# christmas_card.net
KiCad netlist of a schematic drawn in EAGLE
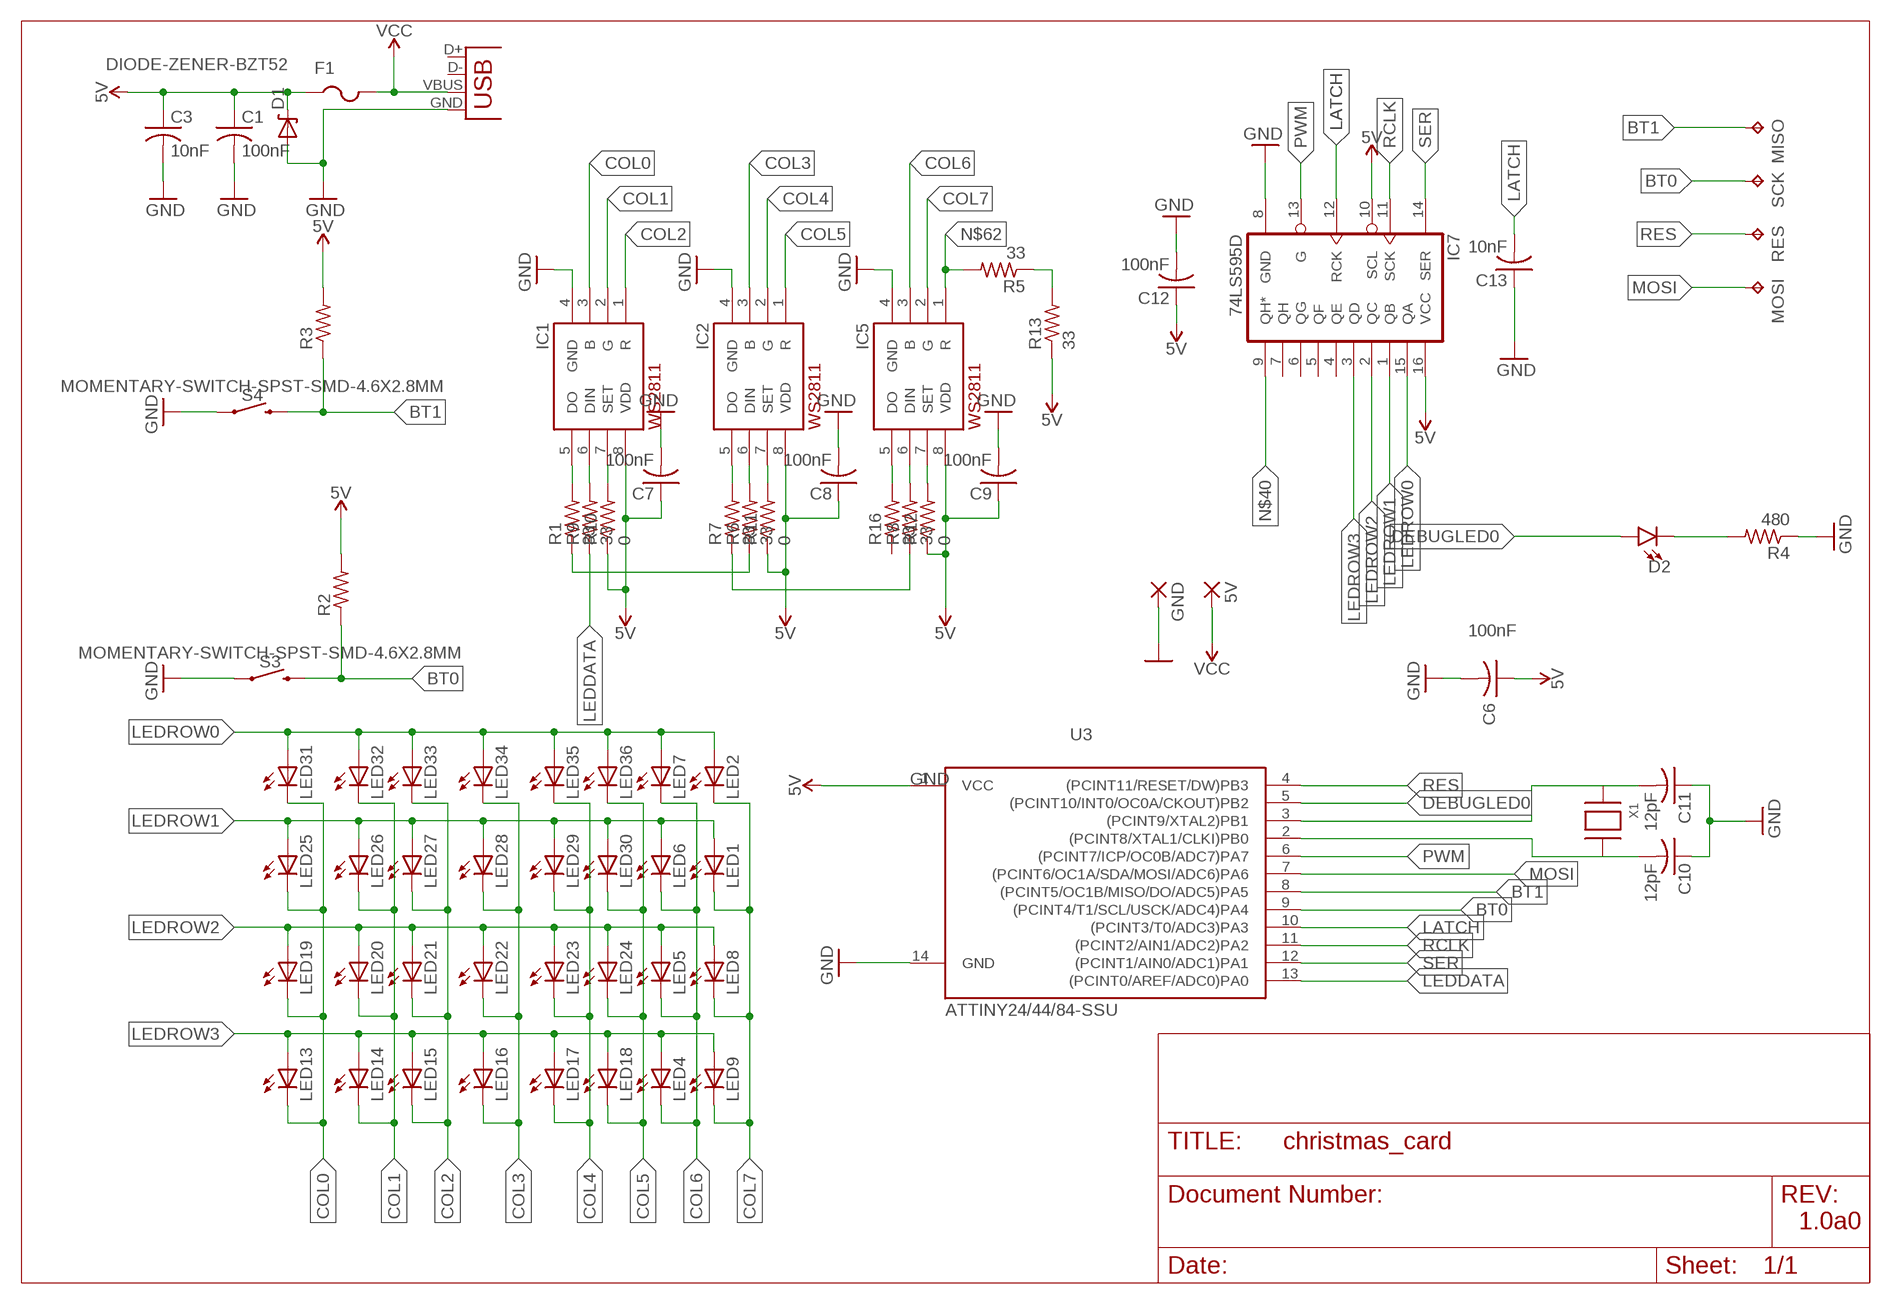
[diagram p0: schematic, sheet 1]

(export (version "E")
  (design (tool "Eeschema 10.0.6"))
  (components
    (comp (ref "5V")
      (value "WIREPADSMD2,54-5,08")
      (footprint "eagle-import:SMD2,54-5,08")
      (libsource (lib "eagle-import") (part "WIREPADSMD2,54-5,08"))
    )
    (comp (ref "C1")
      (value "100nF")
      (footprint "eagle-import:C0603")
      (libsource (lib "eagle-import") (part "C-USC0603"))
    )
    (comp (ref "C3")
      (value "10nF")
      (footprint "eagle-import:C0603")
      (libsource (lib "eagle-import") (part "C-USC0603"))
    )
    (comp (ref "C6")
      (value "100nF")
      (footprint "eagle-import:C0603")
      (libsource (lib "eagle-import") (part "C-USC0603"))
    )
    (comp (ref "C7")
      (value "100nF")
      (footprint "eagle-import:C0603")
      (libsource (lib "eagle-import") (part "C-USC0603"))
    )
    (comp (ref "C8")
      (value "100nF")
      (footprint "eagle-import:C0603")
      (libsource (lib "eagle-import") (part "C-USC0603"))
    )
    (comp (ref "C9")
      (value "100nF")
      (footprint "eagle-import:C0603")
      (libsource (lib "eagle-import") (part "C-USC0603"))
    )
    (comp (ref "C10")
      (value "12pF")
      (footprint "eagle-import:C0603")
      (libsource (lib "eagle-import") (part "C-USC0603"))
    )
    (comp (ref "C11")
      (value "12pF")
      (footprint "eagle-import:C0603")
      (libsource (lib "eagle-import") (part "C-USC0603"))
    )
    (comp (ref "C12")
      (value "100nF")
      (footprint "eagle-import:C0603")
      (libsource (lib "eagle-import") (part "C-USC0603"))
    )
    (comp (ref "C13")
      (value "10nF")
      (footprint "eagle-import:C0603")
      (libsource (lib "eagle-import") (part "C-USC0603"))
    )
    (comp (ref "D1")
      (value "DIODE-ZENER-BZT52")
      (footprint "eagle-import:SOD-323")
      (libsource (lib "eagle-import") (part "DIODE-ZENER-BZT52"))
    )
    (comp (ref "D2")
      (value "LED0603")
      (footprint "eagle-import:LED-0603")
      (libsource (lib "eagle-import") (part "SparkFun-LED_529_LED0603"))
    )
    (comp (ref "F1")
      (value "PTCFUSE-1206")
      (footprint "eagle-import:R1206")
      (libsource (lib "eagle-import") (part "PTCFUSE-1206"))
    )
    (comp (ref "GND")
      (value "WIREPADSMD2,54-5,08")
      (footprint "eagle-import:SMD2,54-5,08")
      (libsource (lib "eagle-import") (part "WIREPADSMD2,54-5,08"))
    )
    (comp (ref "IC1")
      (value "WS2811-SOP8")
      (footprint "eagle-import:SO08-SKINNYPADS")
      (libsource (lib "eagle-import") (part "WS2811-SOP8"))
    )
    (comp (ref "IC2")
      (value "WS2811-SOP8")
      (footprint "eagle-import:SO08-SKINNYPADS")
      (libsource (lib "eagle-import") (part "WS2811-SOP8"))
    )
    (comp (ref "IC5")
      (value "WS2811-SOP8")
      (footprint "eagle-import:SO08-SKINNYPADS")
      (libsource (lib "eagle-import") (part "WS2811-SOP8"))
    )
    (comp (ref "IC7")
      (value "74LS595D")
      (footprint "eagle-import:SO16")
      (fields (field (name "SPICEPREFIX") "X"))
      (libsource (lib "eagle-import") (part "74595DLS"))
    )
    (comp (ref "LED1")
      (value "LED1206")
      (footprint "eagle-import:LED-1206")
      (libsource (lib "eagle-import") (part "LED1206"))
    )
    (comp (ref "LED2")
      (value "LED1206")
      (footprint "eagle-import:LED-1206")
      (libsource (lib "eagle-import") (part "LED1206"))
    )
    (comp (ref "LED4")
      (value "LED1206")
      (footprint "eagle-import:LED-1206")
      (libsource (lib "eagle-import") (part "LED1206"))
    )
    (comp (ref "LED5")
      (value "LED1206")
      (footprint "eagle-import:LED-1206")
      (libsource (lib "eagle-import") (part "LED1206"))
    )
    (comp (ref "LED6")
      (value "LED1206")
      (footprint "eagle-import:LED-1206")
      (libsource (lib "eagle-import") (part "LED1206"))
    )
    (comp (ref "LED7")
      (value "LED1206")
      (footprint "eagle-import:LED-1206")
      (libsource (lib "eagle-import") (part "LED1206"))
    )
    (comp (ref "LED8")
      (value "LED1206")
      (footprint "eagle-import:LED-1206")
      (libsource (lib "eagle-import") (part "LED1206"))
    )
    (comp (ref "LED9")
      (value "LED1206")
      (footprint "eagle-import:LED-1206")
      (libsource (lib "eagle-import") (part "LED1206"))
    )
    (comp (ref "LED13")
      (value "LED1206")
      (footprint "eagle-import:LED-1206")
      (libsource (lib "eagle-import") (part "LED1206"))
    )
    (comp (ref "LED14")
      (value "LED1206")
      (footprint "eagle-import:LED-1206")
      (libsource (lib "eagle-import") (part "LED1206"))
    )
    (comp (ref "LED15")
      (value "LED1206")
      (footprint "eagle-import:LED-1206")
      (libsource (lib "eagle-import") (part "LED1206"))
    )
    (comp (ref "LED16")
      (value "LED1206")
      (footprint "eagle-import:LED-1206")
      (libsource (lib "eagle-import") (part "LED1206"))
    )
    (comp (ref "LED17")
      (value "LED1206")
      (footprint "eagle-import:LED-1206")
      (libsource (lib "eagle-import") (part "LED1206"))
    )
    (comp (ref "LED18")
      (value "LED1206")
      (footprint "eagle-import:LED-1206")
      (libsource (lib "eagle-import") (part "LED1206"))
    )
    (comp (ref "LED19")
      (value "LED1206")
      (footprint "eagle-import:LED-1206")
      (libsource (lib "eagle-import") (part "LED1206"))
    )
    (comp (ref "LED20")
      (value "LED1206")
      (footprint "eagle-import:LED-1206")
      (libsource (lib "eagle-import") (part "LED1206"))
    )
    (comp (ref "LED21")
      (value "LED1206")
      (footprint "eagle-import:LED-1206")
      (libsource (lib "eagle-import") (part "LED1206"))
    )
    (comp (ref "LED22")
      (value "LED1206")
      (footprint "eagle-import:LED-1206")
      (libsource (lib "eagle-import") (part "LED1206"))
    )
    (comp (ref "LED23")
      (value "LED1206")
      (footprint "eagle-import:LED-1206")
      (libsource (lib "eagle-import") (part "LED1206"))
    )
    (comp (ref "LED24")
      (value "LED1206")
      (footprint "eagle-import:LED-1206")
      (libsource (lib "eagle-import") (part "LED1206"))
    )
    (comp (ref "LED25")
      (value "LED1206")
      (footprint "eagle-import:LED-1206")
      (libsource (lib "eagle-import") (part "LED1206"))
    )
    (comp (ref "LED26")
      (value "LED1206")
      (footprint "eagle-import:LED-1206")
      (libsource (lib "eagle-import") (part "LED1206"))
    )
    (comp (ref "LED27")
      (value "LED1206")
      (footprint "eagle-import:LED-1206")
      (libsource (lib "eagle-import") (part "LED1206"))
    )
    (comp (ref "LED28")
      (value "LED1206")
      (footprint "eagle-import:LED-1206")
      (libsource (lib "eagle-import") (part "LED1206"))
    )
    (comp (ref "LED29")
      (value "LED1206")
      (footprint "eagle-import:LED-1206")
      (libsource (lib "eagle-import") (part "LED1206"))
    )
    (comp (ref "LED30")
      (value "LED1206")
      (footprint "eagle-import:LED-1206")
      (libsource (lib "eagle-import") (part "LED1206"))
    )
    (comp (ref "LED31")
      (value "LED1206")
      (footprint "eagle-import:LED-1206")
      (libsource (lib "eagle-import") (part "LED1206"))
    )
    (comp (ref "LED32")
      (value "LED1206")
      (footprint "eagle-import:LED-1206")
      (libsource (lib "eagle-import") (part "LED1206"))
    )
    (comp (ref "LED33")
      (value "LED1206")
      (footprint "eagle-import:LED-1206")
      (libsource (lib "eagle-import") (part "LED1206"))
    )
    (comp (ref "LED34")
      (value "LED1206")
      (footprint "eagle-import:LED-1206")
      (libsource (lib "eagle-import") (part "LED1206"))
    )
    (comp (ref "LED35")
      (value "LED1206")
      (footprint "eagle-import:LED-1206")
      (libsource (lib "eagle-import") (part "LED1206"))
    )
    (comp (ref "LED36")
      (value "LED1206")
      (footprint "eagle-import:LED-1206")
      (libsource (lib "eagle-import") (part "LED1206"))
    )
    (comp (ref "MISO")
      (value "TPB1,27")
      (footprint "eagle-import:B1,27")
      (libsource (lib "eagle-import") (part "TPB1,27"))
    )
    (comp (ref "MOSI")
      (value "TPB1,27")
      (footprint "eagle-import:B1,27")
      (libsource (lib "eagle-import") (part "TPB1,27"))
    )
    (comp (ref "R1")
      (value "33")
      (footprint "eagle-import:R0603")
      (libsource (lib "eagle-import") (part "R-US_R0603"))
    )
    (comp (ref "R2")
      (value "R-US_R0603")
      (footprint "eagle-import:R0603")
      (libsource (lib "eagle-import") (part "R-US_R0603"))
    )
    (comp (ref "R3")
      (value "R-US_R0603")
      (footprint "eagle-import:R0603")
      (libsource (lib "eagle-import") (part "R-US_R0603"))
    )
    (comp (ref "R4")
      (value "480")
      (footprint "eagle-import:R0603")
      (libsource (lib "eagle-import") (part "R-US_R0603"))
    )
    (comp (ref "R5")
      (value "33")
      (footprint "eagle-import:R0603")
      (libsource (lib "eagle-import") (part "R-US_R0603"))
    )
    (comp (ref "R6")
      (value "33")
      (footprint "eagle-import:R0603")
      (libsource (lib "eagle-import") (part "R-US_R0603"))
    )
    (comp (ref "R7")
      (value "33")
      (footprint "eagle-import:R0603")
      (libsource (lib "eagle-import") (part "R-US_R0603"))
    )
    (comp (ref "R8")
      (value "33")
      (footprint "eagle-import:R0603")
      (libsource (lib "eagle-import") (part "R-US_R0603"))
    )
    (comp (ref "R9")
      (value "33")
      (footprint "eagle-import:R0603")
      (libsource (lib "eagle-import") (part "R-US_R0603"))
    )
    (comp (ref "R10")
      (value "0")
      (footprint "eagle-import:R0603")
      (libsource (lib "eagle-import") (part "R-US_R0603"))
    )
    (comp (ref "R11")
      (value "0")
      (footprint "eagle-import:R0603")
      (libsource (lib "eagle-import") (part "R-US_R0603"))
    )
    (comp (ref "R12")
      (value "0")
      (footprint "eagle-import:R0603")
      (libsource (lib "eagle-import") (part "R-US_R0603"))
    )
    (comp (ref "R13")
      (value "33")
      (footprint "eagle-import:R0603")
      (libsource (lib "eagle-import") (part "R-US_R0603"))
    )
    (comp (ref "R16")
      (value "33")
      (footprint "eagle-import:R0603")
      (libsource (lib "eagle-import") (part "R-US_R0603"))
    )
    (comp (ref "RES")
      (value "TPB1,27")
      (footprint "eagle-import:B1,27")
      (libsource (lib "eagle-import") (part "TPB1,27"))
    )
    (comp (ref "S3")
      (value "MOMENTARY-SWITCH-SPST-SMD-4.6X2.8MM")
      (footprint "eagle-import:TACTILE_SWITCH_SMD_4.6X2.8MM")
      (libsource (lib "eagle-import") (part "MOMENTARY-SWITCH-SPST-SMD-4.6X2.8MM"))
    )
    (comp (ref "S4")
      (value "MOMENTARY-SWITCH-SPST-SMD-4.6X2.8MM")
      (footprint "eagle-import:TACTILE_SWITCH_SMD_4.6X2.8MM")
      (libsource (lib "eagle-import") (part "MOMENTARY-SWITCH-SPST-SMD-4.6X2.8MM"))
    )
    (comp (ref "SCK")
      (value "TPB1,27")
      (footprint "eagle-import:B1,27")
      (libsource (lib "eagle-import") (part "TPB1,27"))
    )
    (comp (ref "U3")
      (value "ATTINY24/44/84-SSU")
      (footprint "eagle-import:SOIC14N")
      (libsource (lib "eagle-import") (part "ATTINY24/44/84-SSU"))
    )
    (comp (ref "X1")
      (value "XTALNX5032")
      (footprint "eagle-import:NX5032")
      (libsource (lib "eagle-import") (part "XTALNX5032"))
    )
    (comp (ref "X2")
      (value "USB-MICROB")
      (footprint "eagle-import:USB-MICROB")
      (libsource (lib "eagle-import") (part "USB-MICROB"))
    )
  )
  (nets
    (net (code "1") (name "5V") (class "Default")
      (node (ref "C1") (pin "1") (pinfunction "1_1") (pintype "passive"))
      (node (ref "C12") (pin "1") (pinfunction "1_1") (pintype "passive"))
      (node (ref "C3") (pin "1") (pinfunction "1_1") (pintype "passive"))
      (node (ref "C6") (pin "1") (pinfunction "1_1") (pintype "passive"))
      (node (ref "C7") (pin "1") (pinfunction "1_1") (pintype "passive"))
      (node (ref "C8") (pin "1") (pinfunction "1_1") (pintype "passive"))
      (node (ref "C9") (pin "1") (pinfunction "1_1") (pintype "passive"))
      (node (ref "D1") (pin "1") (pinfunction "C_1") (pintype "passive"))
      (node (ref "F1") (pin "1") (pinfunction "1_1") (pintype "passive"))
      (node (ref "IC1") (pin "8") (pinfunction "VDD_8") (pintype "power_in"))
      (node (ref "IC2") (pin "8") (pinfunction "VDD_8") (pintype "power_in"))
      (node (ref "IC5") (pin "8") (pinfunction "VDD_8") (pintype "power_in"))
      (node (ref "IC7") (pin "10") (pinfunction "SCL_10") (pintype "input"))
      (node (ref "IC7") (pin "16") (pinfunction "VCC_16") (pintype "power_in"))
      (node (ref "R10") (pin "1") (pinfunction "1_1") (pintype "passive"))
      (node (ref "R11") (pin "1") (pinfunction "1_1") (pintype "passive"))
      (node (ref "R12") (pin "1") (pinfunction "1_1") (pintype "passive"))
      (node (ref "R13") (pin "1") (pinfunction "1_1") (pintype "passive"))
      (node (ref "R2") (pin "2") (pinfunction "2_2") (pintype "passive"))
      (node (ref "R3") (pin "2") (pinfunction "2_2") (pintype "passive"))
      (node (ref "U3") (pin "1") (pinfunction "VCC_1") (pintype "bidirectional"))
    )
    (net (code "2") (name "BT0") (class "Default")
      (node (ref "R2") (pin "1") (pinfunction "1_1") (pintype "passive"))
      (node (ref "S3") (pin "3") (pinfunction "2_3") (pintype "passive"))
      (node (ref "S3") (pin "4") (pinfunction "2_4") (pintype "passive"))
      (node (ref "SCK") (pin "TP") (pinfunction "TP_TP") (pintype "input"))
      (node (ref "U3") (pin "9") (pinfunction "(PCINT4/T1/SCL/USCK/ADC4)PA4_9") (pintype "bidirectional"))
    )
    (net (code "3") (name "BT1") (class "Default")
      (node (ref "MISO") (pin "TP") (pinfunction "TP_TP") (pintype "input"))
      (node (ref "R3") (pin "1") (pinfunction "1_1") (pintype "passive"))
      (node (ref "S4") (pin "3") (pinfunction "2_3") (pintype "passive"))
      (node (ref "S4") (pin "4") (pinfunction "2_4") (pintype "passive"))
      (node (ref "U3") (pin "8") (pinfunction "(PCINT5/OC1B/MISO/DO/ADC5)PA5_8") (pintype "bidirectional"))
    )
    (net (code "4") (name "COL0") (class "Default")
      (node (ref "IC1") (pin "3") (pinfunction "B_3") (pintype "open_collector"))
      (node (ref "LED13") (pin "C") (pinfunction "C_C") (pintype "passive"))
      (node (ref "LED19") (pin "C") (pinfunction "C_C") (pintype "passive"))
      (node (ref "LED25") (pin "C") (pinfunction "C_C") (pintype "passive"))
      (node (ref "LED31") (pin "C") (pinfunction "C_C") (pintype "passive"))
    )
    (net (code "5") (name "COL1") (class "Default")
      (node (ref "IC1") (pin "2") (pinfunction "G_2") (pintype "open_collector"))
      (node (ref "LED14") (pin "C") (pinfunction "C_C") (pintype "passive"))
      (node (ref "LED20") (pin "C") (pinfunction "C_C") (pintype "passive"))
      (node (ref "LED26") (pin "C") (pinfunction "C_C") (pintype "passive"))
      (node (ref "LED32") (pin "C") (pinfunction "C_C") (pintype "passive"))
    )
    (net (code "6") (name "COL2") (class "Default")
      (node (ref "IC1") (pin "1") (pinfunction "R_1") (pintype "open_collector"))
      (node (ref "LED15") (pin "C") (pinfunction "C_C") (pintype "passive"))
      (node (ref "LED21") (pin "C") (pinfunction "C_C") (pintype "passive"))
      (node (ref "LED27") (pin "C") (pinfunction "C_C") (pintype "passive"))
      (node (ref "LED33") (pin "C") (pinfunction "C_C") (pintype "passive"))
    )
    (net (code "7") (name "COL3") (class "Default")
      (node (ref "IC2") (pin "3") (pinfunction "B_3") (pintype "open_collector"))
      (node (ref "LED16") (pin "C") (pinfunction "C_C") (pintype "passive"))
      (node (ref "LED22") (pin "C") (pinfunction "C_C") (pintype "passive"))
      (node (ref "LED28") (pin "C") (pinfunction "C_C") (pintype "passive"))
      (node (ref "LED34") (pin "C") (pinfunction "C_C") (pintype "passive"))
    )
    (net (code "8") (name "COL4") (class "Default")
      (node (ref "IC2") (pin "2") (pinfunction "G_2") (pintype "open_collector"))
      (node (ref "LED17") (pin "C") (pinfunction "C_C") (pintype "passive"))
      (node (ref "LED23") (pin "C") (pinfunction "C_C") (pintype "passive"))
      (node (ref "LED29") (pin "C") (pinfunction "C_C") (pintype "passive"))
      (node (ref "LED35") (pin "C") (pinfunction "C_C") (pintype "passive"))
    )
    (net (code "9") (name "COL5") (class "Default")
      (node (ref "IC2") (pin "1") (pinfunction "R_1") (pintype "open_collector"))
      (node (ref "LED18") (pin "C") (pinfunction "C_C") (pintype "passive"))
      (node (ref "LED24") (pin "C") (pinfunction "C_C") (pintype "passive"))
      (node (ref "LED30") (pin "C") (pinfunction "C_C") (pintype "passive"))
      (node (ref "LED36") (pin "C") (pinfunction "C_C") (pintype "passive"))
    )
    (net (code "10") (name "COL6") (class "Default")
      (node (ref "IC5") (pin "3") (pinfunction "B_3") (pintype "open_collector"))
      (node (ref "LED4") (pin "C") (pinfunction "C_C") (pintype "passive"))
      (node (ref "LED5") (pin "C") (pinfunction "C_C") (pintype "passive"))
      (node (ref "LED6") (pin "C") (pinfunction "C_C") (pintype "passive"))
      (node (ref "LED7") (pin "C") (pinfunction "C_C") (pintype "passive"))
    )
    (net (code "11") (name "COL7") (class "Default")
      (node (ref "IC5") (pin "2") (pinfunction "G_2") (pintype "open_collector"))
      (node (ref "LED1") (pin "C") (pinfunction "C_C") (pintype "passive"))
      (node (ref "LED2") (pin "C") (pinfunction "C_C") (pintype "passive"))
      (node (ref "LED8") (pin "C") (pinfunction "C_C") (pintype "passive"))
      (node (ref "LED9") (pin "C") (pinfunction "C_C") (pintype "passive"))
    )
    (net (code "12") (name "DEBUGLED0") (class "Default")
      (node (ref "D2") (pin "A") (pinfunction "A_A") (pintype "passive"))
      (node (ref "U3") (pin "5") (pinfunction "(PCINT10/INT0/OC0A/CKOUT)PB2_5") (pintype "bidirectional"))
    )
    (net (code "13") (name "GND") (class "Default")
      (node (ref "C1") (pin "2") (pinfunction "2_2") (pintype "passive"))
      (node (ref "C10") (pin "1") (pinfunction "1_1") (pintype "passive"))
      (node (ref "C11") (pin "1") (pinfunction "1_1") (pintype "passive"))
      (node (ref "C12") (pin "2") (pinfunction "2_2") (pintype "passive"))
      (node (ref "C13") (pin "1") (pinfunction "1_1") (pintype "passive"))
      (node (ref "C3") (pin "2") (pinfunction "2_2") (pintype "passive"))
      (node (ref "C6") (pin "2") (pinfunction "2_2") (pintype "passive"))
      (node (ref "C7") (pin "2") (pinfunction "2_2") (pintype "passive"))
      (node (ref "C8") (pin "2") (pinfunction "2_2") (pintype "passive"))
      (node (ref "C9") (pin "2") (pinfunction "2_2") (pintype "passive"))
      (node (ref "D1") (pin "2") (pinfunction "A_2") (pintype "passive"))
      (node (ref "GND") (pin "1") (pinfunction "P_1") (pintype "passive"))
      (node (ref "IC1") (pin "4") (pinfunction "GND_4") (pintype "power_in"))
      (node (ref "IC2") (pin "4") (pinfunction "GND_4") (pintype "power_in"))
      (node (ref "IC5") (pin "4") (pinfunction "GND_4") (pintype "power_in"))
      (node (ref "IC7") (pin "8") (pinfunction "GND_8") (pintype "power_in"))
      (node (ref "R4") (pin "1") (pinfunction "1_1") (pintype "passive"))
      (node (ref "S3") (pin "1") (pinfunction "1_1") (pintype "passive"))
      (node (ref "S3") (pin "2") (pinfunction "1_2") (pintype "passive"))
      (node (ref "S4") (pin "1") (pinfunction "1_1") (pintype "passive"))
      (node (ref "S4") (pin "2") (pinfunction "1_2") (pintype "passive"))
      (node (ref "U3") (pin "14") (pinfunction "GND_14") (pintype "bidirectional"))
      (node (ref "X2") (pin "GND") (pinfunction "GND_GND") (pintype "bidirectional"))
    )
    (net (code "14") (name "LATCH") (class "Default")
      (node (ref "C13") (pin "2") (pinfunction "2_2") (pintype "passive"))
      (node (ref "IC7") (pin "12") (pinfunction "RCK_12") (pintype "input"))
      (node (ref "U3") (pin "10") (pinfunction "(PCINT3/T0/ADC3)PA3_10") (pintype "bidirectional"))
    )
    (net (code "15") (name "LEDDATA") (class "Default")
      (node (ref "R9") (pin "1") (pinfunction "1_1") (pintype "passive"))
      (node (ref "U3") (pin "13") (pinfunction "(PCINT0/AREF/ADC0)PA0_13") (pintype "bidirectional"))
    )
    (net (code "16") (name "LEDROW0") (class "Default")
      (node (ref "IC7") (pin "15") (pinfunction "QA_15") (pintype "tri_state"))
      (node (ref "LED2") (pin "A") (pinfunction "A_A") (pintype "passive"))
      (node (ref "LED31") (pin "A") (pinfunction "A_A") (pintype "passive"))
      (node (ref "LED32") (pin "A") (pinfunction "A_A") (pintype "passive"))
      (node (ref "LED33") (pin "A") (pinfunction "A_A") (pintype "passive"))
      (node (ref "LED34") (pin "A") (pinfunction "A_A") (pintype "passive"))
      (node (ref "LED35") (pin "A") (pinfunction "A_A") (pintype "passive"))
      (node (ref "LED36") (pin "A") (pinfunction "A_A") (pintype "passive"))
      (node (ref "LED7") (pin "A") (pinfunction "A_A") (pintype "passive"))
    )
    (net (code "17") (name "LEDROW1") (class "Default")
      (node (ref "IC7") (pin "1") (pinfunction "QB_1") (pintype "tri_state"))
      (node (ref "LED1") (pin "A") (pinfunction "A_A") (pintype "passive"))
      (node (ref "LED25") (pin "A") (pinfunction "A_A") (pintype "passive"))
      (node (ref "LED26") (pin "A") (pinfunction "A_A") (pintype "passive"))
      (node (ref "LED27") (pin "A") (pinfunction "A_A") (pintype "passive"))
      (node (ref "LED28") (pin "A") (pinfunction "A_A") (pintype "passive"))
      (node (ref "LED29") (pin "A") (pinfunction "A_A") (pintype "passive"))
      (node (ref "LED30") (pin "A") (pinfunction "A_A") (pintype "passive"))
      (node (ref "LED6") (pin "A") (pinfunction "A_A") (pintype "passive"))
    )
    (net (code "18") (name "LEDROW2") (class "Default")
      (node (ref "IC7") (pin "2") (pinfunction "QC_2") (pintype "tri_state"))
      (node (ref "LED19") (pin "A") (pinfunction "A_A") (pintype "passive"))
      (node (ref "LED20") (pin "A") (pinfunction "A_A") (pintype "passive"))
      (node (ref "LED21") (pin "A") (pinfunction "A_A") (pintype "passive"))
      (node (ref "LED22") (pin "A") (pinfunction "A_A") (pintype "passive"))
      (node (ref "LED23") (pin "A") (pinfunction "A_A") (pintype "passive"))
      (node (ref "LED24") (pin "A") (pinfunction "A_A") (pintype "passive"))
      (node (ref "LED5") (pin "A") (pinfunction "A_A") (pintype "passive"))
      (node (ref "LED8") (pin "A") (pinfunction "A_A") (pintype "passive"))
    )
    (net (code "19") (name "LEDROW3") (class "Default")
      (node (ref "IC7") (pin "3") (pinfunction "QD_3") (pintype "tri_state"))
      (node (ref "LED13") (pin "A") (pinfunction "A_A") (pintype "passive"))
      (node (ref "LED14") (pin "A") (pinfunction "A_A") (pintype "passive"))
      (node (ref "LED15") (pin "A") (pinfunction "A_A") (pintype "passive"))
      (node (ref "LED16") (pin "A") (pinfunction "A_A") (pintype "passive"))
      (node (ref "LED17") (pin "A") (pinfunction "A_A") (pintype "passive"))
      (node (ref "LED18") (pin "A") (pinfunction "A_A") (pintype "passive"))
      (node (ref "LED4") (pin "A") (pinfunction "A_A") (pintype "passive"))
      (node (ref "LED9") (pin "A") (pinfunction "A_A") (pintype "passive"))
    )
    (net (code "20") (name "MOSI") (class "Default")
      (node (ref "MOSI") (pin "TP") (pinfunction "TP_TP") (pintype "input"))
      (node (ref "U3") (pin "7") (pinfunction "(PCINT6/OC1A/SDA/MOSI/ADC6)PA6_7") (pintype "bidirectional"))
    )
    (net (code "21") (name "N$40") (class "Default")
      (node (ref "IC7") (pin "9") (pinfunction "QH*_9") (pintype "tri_state"))
    )
    (net (code "22") (name "N$62") (class "Default")
      (node (ref "IC5") (pin "1") (pinfunction "R_1") (pintype "open_collector"))
      (node (ref "R5") (pin "2") (pinfunction "2_2") (pintype "passive"))
    )
    (net (code "23") (name "Net-(D2-PadC)") (class "Default")
      (node (ref "D2") (pin "C") (pinfunction "C_C") (pintype "passive"))
      (node (ref "R4") (pin "2") (pinfunction "2_2") (pintype "passive"))
    )
    (net (code "24") (name "Net-(IC1-DIN)") (class "Default")
      (node (ref "IC1") (pin "6") (pinfunction "DIN_6") (pintype "input"))
      (node (ref "R9") (pin "2") (pinfunction "2_2") (pintype "passive"))
    )
    (net (code "25") (name "Net-(IC1-DO)") (class "Default")
      (node (ref "IC1") (pin "5") (pinfunction "DO_5") (pintype "output"))
      (node (ref "R1") (pin "2") (pinfunction "2_2") (pintype "passive"))
    )
    (net (code "26") (name "Net-(IC1-SET)") (class "Default")
      (node (ref "IC1") (pin "7") (pinfunction "SET_7") (pintype "input"))
      (node (ref "R10") (pin "2") (pinfunction "2_2") (pintype "passive"))
    )
    (net (code "27") (name "Net-(IC2-DIN)") (class "Default")
      (node (ref "IC2") (pin "6") (pinfunction "DIN_6") (pintype "input"))
      (node (ref "R6") (pin "2") (pinfunction "2_2") (pintype "passive"))
    )
    (net (code "28") (name "Net-(IC2-DO)") (class "Default")
      (node (ref "IC2") (pin "5") (pinfunction "DO_5") (pintype "output"))
      (node (ref "R7") (pin "2") (pinfunction "2_2") (pintype "passive"))
    )
    (net (code "29") (name "Net-(IC2-SET)") (class "Default")
      (node (ref "IC2") (pin "7") (pinfunction "SET_7") (pintype "input"))
      (node (ref "R11") (pin "2") (pinfunction "2_2") (pintype "passive"))
    )
    (net (code "30") (name "Net-(IC5-DIN)") (class "Default")
      (node (ref "IC5") (pin "6") (pinfunction "DIN_6") (pintype "input"))
      (node (ref "R8") (pin "2") (pinfunction "2_2") (pintype "passive"))
    )
    (net (code "31") (name "Net-(IC5-DO)") (class "Default")
      (node (ref "IC5") (pin "5") (pinfunction "DO_5") (pintype "output"))
      (node (ref "R16") (pin "2") (pinfunction "2_2") (pintype "passive"))
    )
    (net (code "32") (name "Net-(IC5-SET)") (class "Default")
      (node (ref "IC5") (pin "7") (pinfunction "SET_7") (pintype "input"))
      (node (ref "R12") (pin "2") (pinfunction "2_2") (pintype "passive"))
    )
    (net (code "33") (name "Net-(R1-Pad1)") (class "Default")
      (node (ref "R1") (pin "1") (pinfunction "1_1") (pintype "passive"))
      (node (ref "R6") (pin "1") (pinfunction "1_1") (pintype "passive"))
    )
    (net (code "34") (name "Net-(R7-Pad1)") (class "Default")
      (node (ref "R7") (pin "1") (pinfunction "1_1") (pintype "passive"))
      (node (ref "R8") (pin "1") (pinfunction "1_1") (pintype "passive"))
    )
    (net (code "35") (name "Net-(R13-Pad2)") (class "Default")
      (node (ref "R13") (pin "2") (pinfunction "2_2") (pintype "passive"))
      (node (ref "R5") (pin "1") (pinfunction "1_1") (pintype "passive"))
    )
    (net (code "36") (name "Net-(U3-(PCINT8{slash}XTAL1{slash}CLKI)PB0)") (class "Default")
      (node (ref "C10") (pin "2") (pinfunction "2_2") (pintype "passive"))
      (node (ref "U3") (pin "2") (pinfunction "(PCINT8/XTAL1/CLKI)PB0_2") (pintype "bidirectional"))
      (node (ref "X1") (pin "P$2") (pinfunction "P$2_P$2") (pintype "bidirectional"))
    )
    (net (code "37") (name "Net-(U3-(PCINT9{slash}XTAL2)PB1)") (class "Default")
      (node (ref "C11") (pin "2") (pinfunction "2_2") (pintype "passive"))
      (node (ref "U3") (pin "3") (pinfunction "(PCINT9/XTAL2)PB1_3") (pintype "bidirectional"))
      (node (ref "X1") (pin "P$1") (pinfunction "P$1_P$1") (pintype "bidirectional"))
    )
    (net (code "38") (name "PWM") (class "Default")
      (node (ref "IC7") (pin "13") (pinfunction "G_13") (pintype "input"))
      (node (ref "U3") (pin "6") (pinfunction "(PCINT7/ICP/OC0B/ADC7)PA7_6") (pintype "bidirectional"))
    )
    (net (code "39") (name "RCLK") (class "Default")
      (node (ref "IC7") (pin "11") (pinfunction "SCK_11") (pintype "input"))
      (node (ref "U3") (pin "11") (pinfunction "(PCINT2/AIN1/ADC2)PA2_11") (pintype "bidirectional"))
    )
    (net (code "40") (name "RES") (class "Default")
      (node (ref "RES") (pin "TP") (pinfunction "TP_TP") (pintype "input"))
      (node (ref "U3") (pin "4") (pinfunction "(PCINT11/RESET/DW)PB3_4") (pintype "bidirectional"))
    )
    (net (code "41") (name "SER") (class "Default")
      (node (ref "IC7") (pin "14") (pinfunction "SER_14") (pintype "input"))
      (node (ref "U3") (pin "12") (pinfunction "(PCINT1/AIN0/ADC1)PA1_12") (pintype "bidirectional"))
    )
    (net (code "42") (name "VCC") (class "Default")
      (node (ref "5V") (pin "1") (pinfunction "P_1") (pintype "passive"))
      (node (ref "F1") (pin "2") (pinfunction "2_2") (pintype "passive"))
      (node (ref "X2") (pin "VBUS") (pinfunction "VBUS_VBUS") (pintype "bidirectional"))
    )
    (net (code "43") (name "unconnected-(IC7-QE-Pad4)") (class "Default")
      (node (ref "IC7") (pin "4") (pinfunction "QE_4") (pintype "tri_state"))
    )
    (net (code "44") (name "unconnected-(IC7-QF-Pad5)") (class "Default")
      (node (ref "IC7") (pin "5") (pinfunction "QF_5") (pintype "tri_state"))
    )
    (net (code "45") (name "unconnected-(IC7-QG-Pad6)") (class "Default")
      (node (ref "IC7") (pin "6") (pinfunction "QG_6") (pintype "tri_state"))
    )
    (net (code "46") (name "unconnected-(IC7-QH-Pad7)") (class "Default")
      (node (ref "IC7") (pin "7") (pinfunction "QH_7") (pintype "tri_state"))
    )
    (net (code "47") (name "unconnected-(R16-Pad1)") (class "Default")
      (node (ref "R16") (pin "1") (pinfunction "1_1") (pintype "passive"))
    )
    (net (code "48") (name "unconnected-(X2-PadD+)") (class "Default")
      (node (ref "X2") (pin "D+") (pinfunction "D+_D+") (pintype "bidirectional"))
    )
    (net (code "49") (name "unconnected-(X2-PadD-)") (class "Default")
      (node (ref "X2") (pin "D-") (pinfunction "D-_D-") (pintype "bidirectional"))
    )
  )
)
